# ledlamp.net
KiCad netlist of a schematic drawn in EAGLE
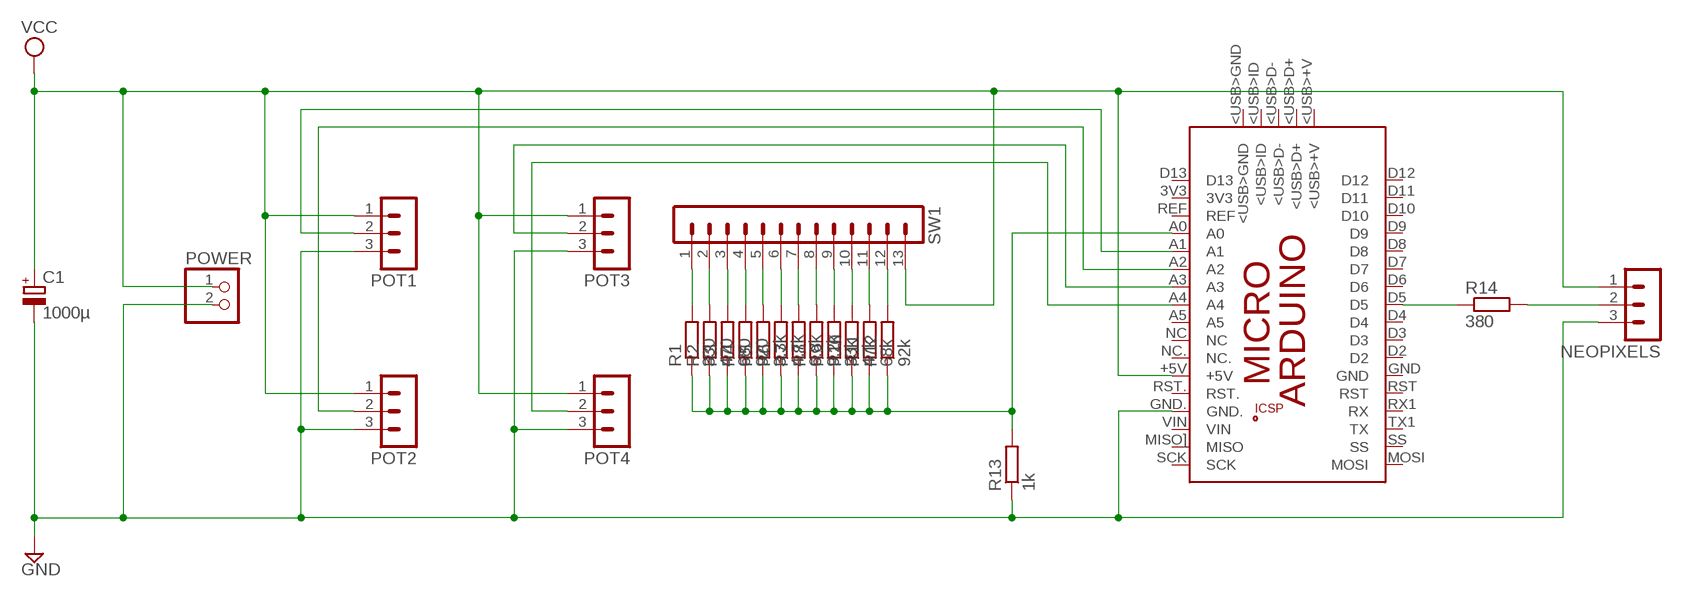
[diagram p0: schematic, sheet 1]

(export (version "E")
  (design (tool "Eeschema 10.0.6"))
  (components
    (comp (ref "C1")
      (value "1000µ")
      (footprint "eagle-import:E5-8,5")
      (libsource (lib "eagle-import") (part "CPOL-EUE5-8.5"))
    )
    (comp (ref "NEOPIXELS")
      (value "MA03-1")
      (footprint "eagle-import:MA03-1")
      (libsource (lib "eagle-import") (part "MA03-1"))
    )
    (comp (ref "PCB1")
      (value "ARDUINO_MICRO")
      (footprint "eagle-import:ARDUINO_MICRO")
      (libsource (lib "eagle-import") (part "ARDUINO_MICRO"))
    )
    (comp (ref "POT1")
      (value "MA03-1")
      (footprint "eagle-import:MA03-1")
      (libsource (lib "eagle-import") (part "MA03-1"))
    )
    (comp (ref "POT2")
      (value "MA03-1")
      (footprint "eagle-import:MA03-1")
      (libsource (lib "eagle-import") (part "MA03-1"))
    )
    (comp (ref "POT3")
      (value "MA03-1")
      (footprint "eagle-import:MA03-1")
      (libsource (lib "eagle-import") (part "MA03-1"))
    )
    (comp (ref "POT4")
      (value "MA03-1")
      (footprint "eagle-import:MA03-1")
      (libsource (lib "eagle-import") (part "MA03-1"))
    )
    (comp (ref "POWER")
      (value "PINHD-1X2")
      (footprint "eagle-import:1X02")
      (libsource (lib "eagle-import") (part "PINHD-1X2"))
    )
    (comp (ref "R1")
      (value "330")
      (footprint "eagle-import:0207_10")
      (libsource (lib "eagle-import") (part "R-EU_0207/10"))
    )
    (comp (ref "R2")
      (value "470")
      (footprint "eagle-import:0207_10")
      (libsource (lib "eagle-import") (part "R-EU_0207/10"))
    )
    (comp (ref "R3")
      (value "680")
      (footprint "eagle-import:0207_10")
      (libsource (lib "eagle-import") (part "R-EU_0207/10"))
    )
    (comp (ref "R4")
      (value "920")
      (footprint "eagle-import:0207_10")
      (libsource (lib "eagle-import") (part "R-EU_0207/10"))
    )
    (comp (ref "R5")
      (value "3.3k")
      (footprint "eagle-import:0207_10")
      (libsource (lib "eagle-import") (part "R-EU_0207/10"))
    )
    (comp (ref "R6")
      (value "4.7k")
      (footprint "eagle-import:0207_10")
      (libsource (lib "eagle-import") (part "R-EU_0207/10"))
    )
    (comp (ref "R7")
      (value "6.8k")
      (footprint "eagle-import:0207_10")
      (libsource (lib "eagle-import") (part "R-EU_0207/10"))
    )
    (comp (ref "R8")
      (value "9.2k")
      (footprint "eagle-import:0207_10")
      (libsource (lib "eagle-import") (part "R-EU_0207/10"))
    )
    (comp (ref "R9")
      (value "33k")
      (footprint "eagle-import:0207_10")
      (libsource (lib "eagle-import") (part "R-EU_0207/10"))
    )
    (comp (ref "R10")
      (value "47k")
      (footprint "eagle-import:0207_10")
      (libsource (lib "eagle-import") (part "R-EU_0207/10"))
    )
    (comp (ref "R11")
      (value "68k")
      (footprint "eagle-import:0207_10")
      (libsource (lib "eagle-import") (part "R-EU_0207/10"))
    )
    (comp (ref "R12")
      (value "92k")
      (footprint "eagle-import:0207_10")
      (libsource (lib "eagle-import") (part "R-EU_0207/10"))
    )
    (comp (ref "R13")
      (value "1k")
      (footprint "eagle-import:0207_10")
      (libsource (lib "eagle-import") (part "R-EU_0207/10"))
    )
    (comp (ref "R14")
      (value "380")
      (footprint "eagle-import:0207_10")
      (libsource (lib "eagle-import") (part "R-EU_0207/10"))
    )
    (comp (ref "SW1")
      (value "MA13-1")
      (footprint "eagle-import:MA13-1")
      (libsource (lib "eagle-import") (part "MA13-1"))
    )
  )
  (nets
    (net (code "1") (name "GND") (class "Default")
      (node (ref "C1") (pin "-") (pinfunction "-_-") (pintype "passive"))
      (node (ref "NEOPIXELS") (pin "3") (pinfunction "3_3") (pintype "passive"))
      (node (ref "PCB1") (pin "GND.") (pinfunction "GND._GND.") (pintype "bidirectional"))
      (node (ref "POT1") (pin "3") (pinfunction "3_3") (pintype "passive"))
      (node (ref "POT2") (pin "3") (pinfunction "3_3") (pintype "passive"))
      (node (ref "POT3") (pin "3") (pinfunction "3_3") (pintype "passive"))
      (node (ref "POT4") (pin "3") (pinfunction "3_3") (pintype "passive"))
      (node (ref "POWER") (pin "2") (pinfunction "2_2") (pintype "passive"))
      (node (ref "R13") (pin "1") (pinfunction "1_1") (pintype "passive"))
    )
    (net (code "2") (name "Net-(NEOPIXELS-Pad2)") (class "Default")
      (node (ref "NEOPIXELS") (pin "2") (pinfunction "2_2") (pintype "passive"))
      (node (ref "R14") (pin "2") (pinfunction "2_2") (pintype "passive"))
    )
    (net (code "3") (name "Net-(PCB1-PadA0)") (class "Default")
      (node (ref "PCB1") (pin "A0") (pinfunction "A0_A0") (pintype "bidirectional"))
      (node (ref "R1") (pin "1") (pinfunction "1_1") (pintype "passive"))
      (node (ref "R10") (pin "1") (pinfunction "1_1") (pintype "passive"))
      (node (ref "R11") (pin "1") (pinfunction "1_1") (pintype "passive"))
      (node (ref "R12") (pin "1") (pinfunction "1_1") (pintype "passive"))
      (node (ref "R13") (pin "2") (pinfunction "2_2") (pintype "passive"))
      (node (ref "R2") (pin "1") (pinfunction "1_1") (pintype "passive"))
      (node (ref "R3") (pin "1") (pinfunction "1_1") (pintype "passive"))
      (node (ref "R4") (pin "1") (pinfunction "1_1") (pintype "passive"))
      (node (ref "R5") (pin "1") (pinfunction "1_1") (pintype "passive"))
      (node (ref "R6") (pin "1") (pinfunction "1_1") (pintype "passive"))
      (node (ref "R7") (pin "1") (pinfunction "1_1") (pintype "passive"))
      (node (ref "R8") (pin "1") (pinfunction "1_1") (pintype "passive"))
      (node (ref "R9") (pin "1") (pinfunction "1_1") (pintype "passive"))
    )
    (net (code "4") (name "Net-(PCB1-PadA1)") (class "Default")
      (node (ref "PCB1") (pin "A1") (pinfunction "A1_A1") (pintype "bidirectional"))
      (node (ref "POT1") (pin "2") (pinfunction "2_2") (pintype "passive"))
    )
    (net (code "5") (name "Net-(PCB1-PadA2)") (class "Default")
      (node (ref "PCB1") (pin "A2") (pinfunction "A2_A2") (pintype "bidirectional"))
      (node (ref "POT2") (pin "2") (pinfunction "2_2") (pintype "passive"))
    )
    (net (code "6") (name "Net-(PCB1-PadA3)") (class "Default")
      (node (ref "PCB1") (pin "A3") (pinfunction "A3_A3") (pintype "bidirectional"))
      (node (ref "POT3") (pin "2") (pinfunction "2_2") (pintype "passive"))
    )
    (net (code "7") (name "Net-(PCB1-PadA4)") (class "Default")
      (node (ref "PCB1") (pin "A4") (pinfunction "A4_A4") (pintype "bidirectional"))
      (node (ref "POT4") (pin "2") (pinfunction "2_2") (pintype "passive"))
    )
    (net (code "8") (name "Net-(PCB1-PadD5)") (class "Default")
      (node (ref "PCB1") (pin "D5") (pinfunction "D5_D5") (pintype "bidirectional"))
      (node (ref "R14") (pin "1") (pinfunction "1_1") (pintype "passive"))
    )
    (net (code "9") (name "Net-(R1-Pad2)") (class "Default")
      (node (ref "R1") (pin "2") (pinfunction "2_2") (pintype "passive"))
      (node (ref "SW1") (pin "1") (pinfunction "1_1") (pintype "passive"))
    )
    (net (code "10") (name "Net-(R2-Pad2)") (class "Default")
      (node (ref "R2") (pin "2") (pinfunction "2_2") (pintype "passive"))
      (node (ref "SW1") (pin "2") (pinfunction "2_2") (pintype "passive"))
    )
    (net (code "11") (name "Net-(R3-Pad2)") (class "Default")
      (node (ref "R3") (pin "2") (pinfunction "2_2") (pintype "passive"))
      (node (ref "SW1") (pin "3") (pinfunction "3_3") (pintype "passive"))
    )
    (net (code "12") (name "Net-(R4-Pad2)") (class "Default")
      (node (ref "R4") (pin "2") (pinfunction "2_2") (pintype "passive"))
      (node (ref "SW1") (pin "4") (pinfunction "4_4") (pintype "passive"))
    )
    (net (code "13") (name "Net-(R5-Pad2)") (class "Default")
      (node (ref "R5") (pin "2") (pinfunction "2_2") (pintype "passive"))
      (node (ref "SW1") (pin "5") (pinfunction "5_5") (pintype "passive"))
    )
    (net (code "14") (name "Net-(R6-Pad2)") (class "Default")
      (node (ref "R6") (pin "2") (pinfunction "2_2") (pintype "passive"))
      (node (ref "SW1") (pin "6") (pinfunction "6_6") (pintype "passive"))
    )
    (net (code "15") (name "Net-(R7-Pad2)") (class "Default")
      (node (ref "R7") (pin "2") (pinfunction "2_2") (pintype "passive"))
      (node (ref "SW1") (pin "7") (pinfunction "7_7") (pintype "passive"))
    )
    (net (code "16") (name "Net-(R8-Pad2)") (class "Default")
      (node (ref "R8") (pin "2") (pinfunction "2_2") (pintype "passive"))
      (node (ref "SW1") (pin "8") (pinfunction "8_8") (pintype "passive"))
    )
    (net (code "17") (name "Net-(R9-Pad2)") (class "Default")
      (node (ref "R9") (pin "2") (pinfunction "2_2") (pintype "passive"))
      (node (ref "SW1") (pin "9") (pinfunction "9_9") (pintype "passive"))
    )
    (net (code "18") (name "Net-(R10-Pad2)") (class "Default")
      (node (ref "R10") (pin "2") (pinfunction "2_2") (pintype "passive"))
      (node (ref "SW1") (pin "10") (pinfunction "10_10") (pintype "passive"))
    )
    (net (code "19") (name "Net-(R11-Pad2)") (class "Default")
      (node (ref "R11") (pin "2") (pinfunction "2_2") (pintype "passive"))
      (node (ref "SW1") (pin "11") (pinfunction "11_11") (pintype "passive"))
    )
    (net (code "20") (name "Net-(R12-Pad2)") (class "Default")
      (node (ref "R12") (pin "2") (pinfunction "2_2") (pintype "passive"))
      (node (ref "SW1") (pin "12") (pinfunction "12_12") (pintype "passive"))
    )
    (net (code "21") (name "VCC") (class "Default")
      (node (ref "C1") (pin "+") (pinfunction "+_+") (pintype "passive"))
      (node (ref "NEOPIXELS") (pin "1") (pinfunction "1_1") (pintype "passive"))
      (node (ref "PCB1") (pin "+5V") (pinfunction "+5V_+5V") (pintype "bidirectional"))
      (node (ref "POT1") (pin "1") (pinfunction "1_1") (pintype "passive"))
      (node (ref "POT2") (pin "1") (pinfunction "1_1") (pintype "passive"))
      (node (ref "POT3") (pin "1") (pinfunction "1_1") (pintype "passive"))
      (node (ref "POT4") (pin "1") (pinfunction "1_1") (pintype "passive"))
      (node (ref "POWER") (pin "1") (pinfunction "1_1") (pintype "passive"))
      (node (ref "SW1") (pin "13") (pinfunction "13_13") (pintype "passive"))
    )
    (net (code "22") (name "unconnected-(PCB1-MISO-PadMISO])") (class "Default")
      (node (ref "PCB1") (pin "MISO]") (pinfunction "MISO_MISO]") (pintype "bidirectional"))
    )
    (net (code "23") (name "unconnected-(PCB1-Pad3V3)") (class "Default")
      (node (ref "PCB1") (pin "3V3") (pinfunction "3V3_3V3") (pintype "bidirectional"))
    )
    (net (code "24") (name "unconnected-(PCB1-Pad5V)") (class "Default")
      (node (ref "PCB1") (pin "5V") (pinfunction "5V_5V") (pintype "bidirectional"))
    )
    (net (code "25") (name "unconnected-(PCB1-Pad<USB>+V)") (class "Default")
      (node (ref "PCB1") (pin "<USB>+V") (pinfunction "<USB>+V_<USB>+V") (pintype "bidirectional"))
    )
    (net (code "26") (name "unconnected-(PCB1-Pad<USB>D+)") (class "Default")
      (node (ref "PCB1") (pin "<USB>D+") (pinfunction "<USB>D+_<USB>D+") (pintype "bidirectional"))
    )
    (net (code "27") (name "unconnected-(PCB1-Pad<USB>D-)") (class "Default")
      (node (ref "PCB1") (pin "<USB>D-") (pinfunction "<USB>D-_<USB>D-") (pintype "bidirectional"))
    )
    (net (code "28") (name "unconnected-(PCB1-Pad<USB>GND)") (class "Default")
      (node (ref "PCB1") (pin "<USB>GND") (pinfunction "<USB>GND_<USB>GND") (pintype "bidirectional"))
    )
    (net (code "29") (name "unconnected-(PCB1-Pad<USB>ID)") (class "Default")
      (node (ref "PCB1") (pin "<USB>ID") (pinfunction "<USB>ID_<USB>ID") (pintype "bidirectional"))
    )
    (net (code "30") (name "unconnected-(PCB1-PadA5)") (class "Default")
      (node (ref "PCB1") (pin "A5") (pinfunction "A5_A5") (pintype "bidirectional"))
    )
    (net (code "31") (name "unconnected-(PCB1-PadD2)") (class "Default")
      (node (ref "PCB1") (pin "D2") (pinfunction "D2_D2") (pintype "bidirectional"))
    )
    (net (code "32") (name "unconnected-(PCB1-PadD3)") (class "Default")
      (node (ref "PCB1") (pin "D3") (pinfunction "D3_D3") (pintype "bidirectional"))
    )
    (net (code "33") (name "unconnected-(PCB1-PadD4)") (class "Default")
      (node (ref "PCB1") (pin "D4") (pinfunction "D4_D4") (pintype "bidirectional"))
    )
    (net (code "34") (name "unconnected-(PCB1-PadD6)") (class "Default")
      (node (ref "PCB1") (pin "D6") (pinfunction "D6_D6") (pintype "bidirectional"))
    )
    (net (code "35") (name "unconnected-(PCB1-PadD7)") (class "Default")
      (node (ref "PCB1") (pin "D7") (pinfunction "D7_D7") (pintype "bidirectional"))
    )
    (net (code "36") (name "unconnected-(PCB1-PadD8)") (class "Default")
      (node (ref "PCB1") (pin "D8") (pinfunction "D8_D8") (pintype "bidirectional"))
    )
    (net (code "37") (name "unconnected-(PCB1-PadD9)") (class "Default")
      (node (ref "PCB1") (pin "D9") (pinfunction "D9_D9") (pintype "bidirectional"))
    )
    (net (code "38") (name "unconnected-(PCB1-PadD10)") (class "Default")
      (node (ref "PCB1") (pin "D10") (pinfunction "D10_D10") (pintype "bidirectional"))
    )
    (net (code "39") (name "unconnected-(PCB1-PadD11)") (class "Default")
      (node (ref "PCB1") (pin "D11") (pinfunction "D11_D11") (pintype "bidirectional"))
    )
    (net (code "40") (name "unconnected-(PCB1-PadD12)") (class "Default")
      (node (ref "PCB1") (pin "D12") (pinfunction "D12_D12") (pintype "bidirectional"))
    )
    (net (code "41") (name "unconnected-(PCB1-PadD13)") (class "Default")
      (node (ref "PCB1") (pin "D13") (pinfunction "D13_D13") (pintype "bidirectional"))
    )
    (net (code "42") (name "unconnected-(PCB1-PadGND)") (class "Default")
      (node (ref "PCB1") (pin "GND") (pinfunction "GND_GND") (pintype "bidirectional"))
    )
    (net (code "43") (name "unconnected-(PCB1-PadGND_)") (class "Default")
      (node (ref "PCB1") (pin "GND_") (pinfunction "GND__GND_") (pintype "bidirectional"))
    )
    (net (code "44") (name "unconnected-(PCB1-PadMISO.)") (class "Default")
      (node (ref "PCB1") (pin "MISO.") (pinfunction "MISO._MISO.") (pintype "bidirectional"))
    )
    (net (code "45") (name "unconnected-(PCB1-PadMOSI)") (class "Default")
      (node (ref "PCB1") (pin "MOSI") (pinfunction "MOSI_MOSI") (pintype "bidirectional"))
    )
    (net (code "46") (name "unconnected-(PCB1-PadMOSI.)") (class "Default")
      (node (ref "PCB1") (pin "MOSI.") (pinfunction "MOSI._MOSI.") (pintype "bidirectional"))
    )
    (net (code "47") (name "unconnected-(PCB1-PadNC)") (class "Default")
      (node (ref "PCB1") (pin "NC") (pinfunction "NC_NC") (pintype "bidirectional"))
    )
    (net (code "48") (name "unconnected-(PCB1-PadNC.)") (class "Default")
      (node (ref "PCB1") (pin "NC.") (pinfunction "NC._NC.") (pintype "bidirectional"))
    )
    (net (code "49") (name "unconnected-(PCB1-PadREF)") (class "Default")
      (node (ref "PCB1") (pin "REF") (pinfunction "REF_REF") (pintype "bidirectional"))
    )
    (net (code "50") (name "unconnected-(PCB1-PadRESET..)") (class "Default")
      (node (ref "PCB1") (pin "RESET..") (pinfunction "RESET.._RESET..") (pintype "bidirectional"))
    )
    (net (code "51") (name "unconnected-(PCB1-PadRST)") (class "Default")
      (node (ref "PCB1") (pin "RST") (pinfunction "RST_RST") (pintype "bidirectional"))
    )
    (net (code "52") (name "unconnected-(PCB1-PadRST.)") (class "Default")
      (node (ref "PCB1") (pin "RST.") (pinfunction "RST._RST.") (pintype "bidirectional"))
    )
    (net (code "53") (name "unconnected-(PCB1-PadSCK)") (class "Default")
      (node (ref "PCB1") (pin "SCK") (pinfunction "SCK_SCK") (pintype "bidirectional"))
    )
    (net (code "54") (name "unconnected-(PCB1-PadSCK.)") (class "Default")
      (node (ref "PCB1") (pin "SCK.") (pinfunction "SCK._SCK.") (pintype "bidirectional"))
    )
    (net (code "55") (name "unconnected-(PCB1-PadSS)") (class "Default")
      (node (ref "PCB1") (pin "SS") (pinfunction "SS_SS") (pintype "bidirectional"))
    )
    (net (code "56") (name "unconnected-(PCB1-PadVIN)") (class "Default")
      (node (ref "PCB1") (pin "VIN") (pinfunction "VIN_VIN") (pintype "bidirectional"))
    )
    (net (code "57") (name "unconnected-(PCB1-RX-PadRX1)") (class "Default")
      (node (ref "PCB1") (pin "RX1") (pinfunction "RX_RX1") (pintype "bidirectional"))
    )
    (net (code "58") (name "unconnected-(PCB1-TX-PadTX1)") (class "Default")
      (node (ref "PCB1") (pin "TX1") (pinfunction "TX_TX1") (pintype "bidirectional"))
    )
  )
)
